# PowerButton.net
KiCad netlist of a schematic drawn in EAGLE
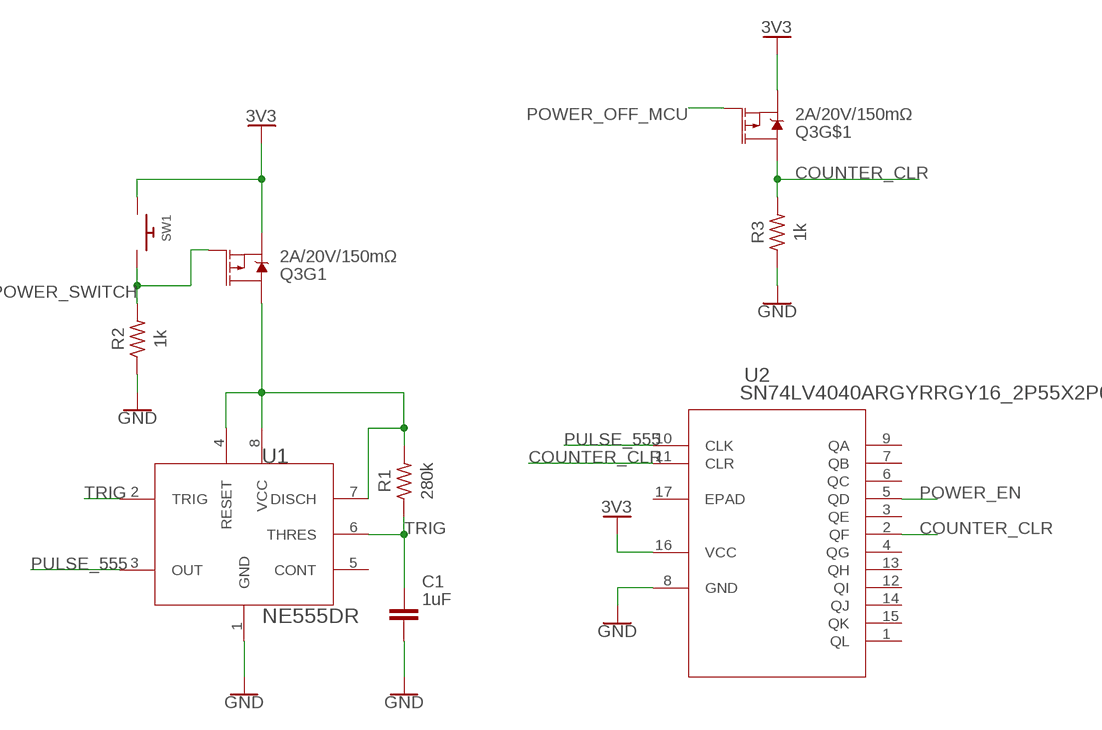
[diagram p0: schematic, sheet 1]

(export (version "E")
  (design (tool "Eeschema 10.0.6"))
  (components
    (comp (ref "C1")
      (value "1uF")
      (footprint "eagle-import:CAPC1608X85")
      (libsource (lib "eagle-import") (part "CCHIP-0603(1608-METRIC)_"))
    )
    (comp (ref "Q3")
      (value "2A/20V/150mΩ")
      (footprint "eagle-import:SOT26")
      (libsource (lib "eagle-import") (part "MOSFET_PCH_DUAL-DMP2240UDM"))
    )
    (comp (ref "R1")
      (value "280k")
      (footprint "eagle-import:RESC1608X60")
      (libsource (lib "eagle-import") (part "R-USCHIP-0603(1608-METRIC)_"))
    )
    (comp (ref "R2")
      (value "1k")
      (footprint "eagle-import:RESC1608X60")
      (libsource (lib "eagle-import") (part "R-USCHIP-0603(1608-METRIC)_"))
    )
    (comp (ref "R3")
      (value "1k")
      (footprint "eagle-import:RESC1608X60")
      (libsource (lib "eagle-import") (part "R-USCHIP-0603(1608-METRIC)_"))
    )
    (comp (ref "SW1")
      (value "SWITCH_PUSHBUTTONSOFTTOUCHSMD_SJ")
      (footprint "eagle-import:PUSHBUTTON_SMD_SJ")
      (libsource (lib "eagle-import") (part "SWITCH_PUSHBUTTONSOFTTOUCHSMD_SJ"))
    )
    (comp (ref "U1")
      (value "NE555DR")
      (footprint "eagle-import:SOIC-8N")
      (fields
        (field (name "DIGI-KEY_PART") "296-6501-1-ND")
        (field (name "MANUFACTURER") "Texas Instruments")
        (field (name "CREATED_BY") "PCBLayout.com")
      )
      (libsource (lib "eagle-import") (part "NE555DR"))
    )
    (comp (ref "U2")
      (value "SN74LV4040ARGYRRGY16_2P55X2P05")
      (footprint "eagle-import:RGY16_2P55X2P05")
      (fields
        (field (name "MANUFACTURER_PART_NUMBER") "SN74LV4040ARGYR")
        (field (name "COPYRIGHT") "Copyright (C) 2024 Ultra Librarian. All rights reserved.")
      )
      (libsource (lib "eagle-import") (part "SN74LV4040ARGYRRGY16_2P55X2P05"))
    )
  )
  (nets
    (net (code "1") (name "/COUNTER_CLR") (class "Default")
      (node (ref "Q3") (pin "D2") (pinfunction "D_D2") (pintype "bidirectional"))
      (node (ref "R3") (pin "2") (pinfunction "2_2") (pintype "passive"))
      (node (ref "U2") (pin "11") (pinfunction "CLR_11") (pintype "input"))
      (node (ref "U2") (pin "2") (pinfunction "QF_2") (pintype "output"))
    )
    (net (code "2") (name "/POWER_EN") (class "Default")
      (node (ref "U2") (pin "5") (pinfunction "QD_5") (pintype "output"))
    )
    (net (code "3") (name "/POWER_OFF_MCU") (class "Default")
      (node (ref "Q3") (pin "G2") (pinfunction "G_G2") (pintype "bidirectional"))
    )
    (net (code "4") (name "/POWER_SWITCH") (class "Default")
      (node (ref "Q3") (pin "G1") (pinfunction "G_G1") (pintype "bidirectional"))
      (node (ref "R2") (pin "2") (pinfunction "2_2") (pintype "passive"))
      (node (ref "SW1") (pin "P$2") (pinfunction "P$2_P$2") (pintype "passive"))
    )
    (net (code "5") (name "/PULSE_555") (class "Default")
      (node (ref "U1") (pin "3") (pinfunction "OUT_3") (pintype "output"))
      (node (ref "U2") (pin "10") (pinfunction "CLK_10") (pintype "input"))
    )
    (net (code "6") (name "/TRIG") (class "Default")
      (node (ref "C1") (pin "1") (pinfunction "1_1") (pintype "passive"))
      (node (ref "R1") (pin "1") (pinfunction "1_1") (pintype "passive"))
      (node (ref "U1") (pin "2") (pinfunction "TRIG_2") (pintype "input"))
      (node (ref "U1") (pin "6") (pinfunction "THRES_6") (pintype "input"))
    )
    (net (code "7") (name "3V3") (class "Default")
      (node (ref "Q3") (pin "S1") (pinfunction "S_S1") (pintype "bidirectional"))
      (node (ref "Q3") (pin "S2") (pinfunction "S_S2") (pintype "bidirectional"))
      (node (ref "SW1") (pin "P$1") (pinfunction "P$1_P$1") (pintype "passive"))
      (node (ref "U2") (pin "16") (pinfunction "VCC_16") (pintype "power_in"))
    )
    (net (code "8") (name "GND") (class "Default")
      (node (ref "C1") (pin "2") (pinfunction "2_2") (pintype "passive"))
      (node (ref "R2") (pin "1") (pinfunction "1_1") (pintype "passive"))
      (node (ref "R3") (pin "1") (pinfunction "1_1") (pintype "passive"))
      (node (ref "U1") (pin "1") (pinfunction "GND_1") (pintype "power_in"))
      (node (ref "U2") (pin "8") (pinfunction "GND_8") (pintype "power_in"))
    )
    (net (code "9") (name "Net-(Q3B-D)") (class "Default")
      (node (ref "Q3") (pin "D1") (pinfunction "D_D1") (pintype "bidirectional"))
      (node (ref "R1") (pin "2") (pinfunction "2_2") (pintype "passive"))
      (node (ref "U1") (pin "4") (pinfunction "RESET_4") (pintype "input"))
      (node (ref "U1") (pin "7") (pinfunction "DISCH_7") (pintype "output"))
      (node (ref "U1") (pin "8") (pinfunction "VCC_8") (pintype "power_in"))
    )
    (net (code "10") (name "unconnected-(U1-CONT-Pad5)") (class "Default")
      (node (ref "U1") (pin "5") (pinfunction "CONT_5") (pintype "bidirectional"))
    )
    (net (code "11") (name "unconnected-(U2-EPAD-Pad17)") (class "Default")
      (node (ref "U2") (pin "17") (pinfunction "EPAD_17") (pintype "passive"))
    )
    (net (code "12") (name "unconnected-(U2-QA-Pad9)") (class "Default")
      (node (ref "U2") (pin "9") (pinfunction "QA_9") (pintype "output"))
    )
    (net (code "13") (name "unconnected-(U2-QB-Pad7)") (class "Default")
      (node (ref "U2") (pin "7") (pinfunction "QB_7") (pintype "output"))
    )
    (net (code "14") (name "unconnected-(U2-QC-Pad6)") (class "Default")
      (node (ref "U2") (pin "6") (pinfunction "QC_6") (pintype "output"))
    )
    (net (code "15") (name "unconnected-(U2-QE-Pad3)") (class "Default")
      (node (ref "U2") (pin "3") (pinfunction "QE_3") (pintype "output"))
    )
    (net (code "16") (name "unconnected-(U2-QG-Pad4)") (class "Default")
      (node (ref "U2") (pin "4") (pinfunction "QG_4") (pintype "output"))
    )
    (net (code "17") (name "unconnected-(U2-QH-Pad13)") (class "Default")
      (node (ref "U2") (pin "13") (pinfunction "QH_13") (pintype "output"))
    )
    (net (code "18") (name "unconnected-(U2-QI-Pad12)") (class "Default")
      (node (ref "U2") (pin "12") (pinfunction "QI_12") (pintype "output"))
    )
    (net (code "19") (name "unconnected-(U2-QJ-Pad14)") (class "Default")
      (node (ref "U2") (pin "14") (pinfunction "QJ_14") (pintype "output"))
    )
    (net (code "20") (name "unconnected-(U2-QK-Pad15)") (class "Default")
      (node (ref "U2") (pin "15") (pinfunction "QK_15") (pintype "output"))
    )
    (net (code "21") (name "unconnected-(U2-QL-Pad1)") (class "Default")
      (node (ref "U2") (pin "1") (pinfunction "QL_1") (pintype "output"))
    )
  )
)
